# V_6.net
KiCad netlist of a schematic drawn in Altium Designer
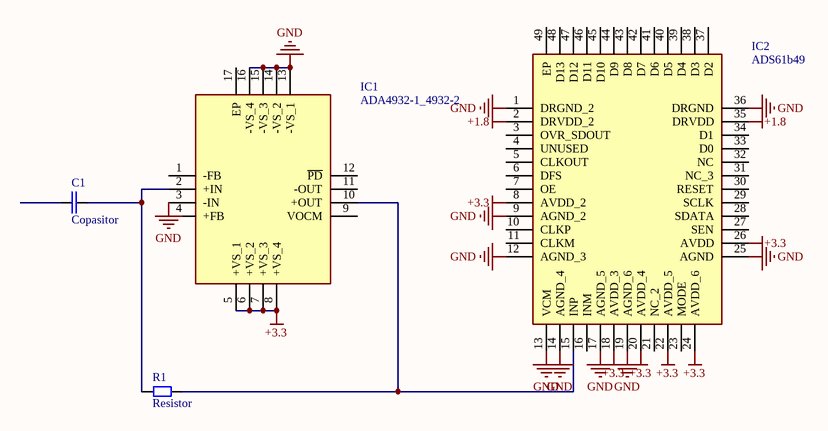
[diagram p0: V_6.SchDoc]

(export (version "E")
  (design (tool "Eeschema 10.0.6"))
  (components
    (comp (ref "C1") (value "Copasitor") (footprint "Copasitor") (libsource (lib "V__6") (part "Copasitor")))
    (comp (ref "IC1")
      (value "ADA4932-1_4932-2")
      (footprint "ADA4932-1")
      (libsource (lib "V__6") (part "ADA4932-1_4932-2"))
    )
    (comp (ref "IC2") (value "ADS61b49") (footprint "ADS61b49") (libsource (lib "V__6") (part "ADS61b49")))
    (comp (ref "R1") (value "Resistor") (footprint "Resistor") (libsource (lib "V__6") (part "Resistor")))
  )
  (nets
    (net (code "1") (name "+1.8") (class "Default")
      (node (ref "IC2") (pin "2") (pinfunction "DRVDD_2_2") (pintype "passive"))
      (node (ref "IC2") (pin "35") (pinfunction "DRVDD_35") (pintype "passive"))
    )
    (net (code "2") (name "+3.3") (class "Default")
      (node (ref "IC1") (pin "5") (pinfunction "+VS_1_5") (pintype "passive"))
      (node (ref "IC1") (pin "6") (pinfunction "+VS_2_6") (pintype "passive"))
      (node (ref "IC1") (pin "7") (pinfunction "+VS_3_7") (pintype "passive"))
      (node (ref "IC1") (pin "8") (pinfunction "+VS_4_8") (pintype "passive"))
      (node (ref "IC2") (pin "18") (pinfunction "AVDD_3_18") (pintype "passive"))
      (node (ref "IC2") (pin "20") (pinfunction "AVDD_4_20") (pintype "passive"))
      (node (ref "IC2") (pin "22") (pinfunction "AVDD_5_22") (pintype "passive"))
      (node (ref "IC2") (pin "24") (pinfunction "AVDD_6_24") (pintype "passive"))
      (node (ref "IC2") (pin "26") (pinfunction "AVDD_26") (pintype "passive"))
      (node (ref "IC2") (pin "8") (pinfunction "AVDD_2_8") (pintype "passive"))
    )
    (net (code "3") (name "GND") (class "Default")
      (node (ref "IC1") (pin "13") (pinfunction "-VS_1_13") (pintype "passive"))
      (node (ref "IC1") (pin "14") (pinfunction "-VS_2_14") (pintype "passive"))
      (node (ref "IC1") (pin "15") (pinfunction "-VS_3_15") (pintype "passive"))
      (node (ref "IC1") (pin "16") (pinfunction "-VS_4_16") (pintype "passive"))
      (node (ref "IC1") (pin "3") (pinfunction "-IN_3") (pintype "passive"))
      (node (ref "IC2") (pin "1") (pinfunction "DRGND_2_1") (pintype "passive"))
      (node (ref "IC2") (pin "12") (pinfunction "AGND_3_12") (pintype "passive"))
      (node (ref "IC2") (pin "13") (pinfunction "VCM_13") (pintype "passive"))
      (node (ref "IC2") (pin "14") (pinfunction "AGND_4_14") (pintype "passive"))
      (node (ref "IC2") (pin "17") (pinfunction "AGND_5_17") (pintype "passive"))
      (node (ref "IC2") (pin "19") (pinfunction "AGND_6_19") (pintype "passive"))
      (node (ref "IC2") (pin "25") (pinfunction "AGND_25") (pintype "passive"))
      (node (ref "IC2") (pin "36") (pinfunction "DRGND_36") (pintype "passive"))
      (node (ref "IC2") (pin "9") (pinfunction "AGND_2_9") (pintype "passive"))
    )
    (net (code "4") (name "Net-(IC1-+IN)") (class "Default")
      (node (ref "C1") (pin "2") (pintype "passive"))
      (node (ref "IC1") (pin "2") (pinfunction "+IN_2") (pintype "passive"))
      (node (ref "R1") (pin "1") (pintype "passive"))
    )
    (net (code "5") (name "Net-(IC1-+OUT)") (class "Default")
      (node (ref "IC1") (pin "10") (pinfunction "+OUT_10") (pintype "passive"))
      (node (ref "IC2") (pin "15") (pinfunction "INP_15") (pintype "passive"))
      (node (ref "R1") (pin "2") (pintype "passive"))
    )
    (net (code "6") (name "unconnected-(C1-Pad1)") (class "Default")
      (node (ref "C1") (pin "1") (pintype "passive"))
    )
    (net (code "7") (name "unconnected-(IC1-+FB-Pad4)") (class "Default")
      (node (ref "IC1") (pin "4") (pinfunction "+FB_4") (pintype "passive"))
    )
    (net (code "8") (name "unconnected-(IC1--FB-Pad1)") (class "Default")
      (node (ref "IC1") (pin "1") (pinfunction "-FB_1") (pintype "passive"))
    )
    (net (code "9") (name "unconnected-(IC1--OUT-Pad11)") (class "Default")
      (node (ref "IC1") (pin "11") (pinfunction "-OUT_11") (pintype "passive"))
    )
    (net (code "10") (name "unconnected-(IC1-EP-Pad17)") (class "Default")
      (node (ref "IC1") (pin "17") (pinfunction "EP_17") (pintype "passive"))
    )
    (net (code "11") (name "unconnected-(IC1-VOCM-Pad9)") (class "Default")
      (node (ref "IC1") (pin "9") (pinfunction "VOCM_9") (pintype "passive"))
    )
    (net (code "12") (name "unconnected-(IC1-~{PD}-Pad12)") (class "Default")
      (node (ref "IC1") (pin "12") (pinfunction "~{PD}_12") (pintype "passive"))
    )
    (net (code "13") (name "unconnected-(IC2-CLKM-Pad11)") (class "Default")
      (node (ref "IC2") (pin "11") (pinfunction "CLKM_11") (pintype "passive"))
    )
    (net (code "14") (name "unconnected-(IC2-CLKOUT-Pad5)") (class "Default")
      (node (ref "IC2") (pin "5") (pinfunction "CLKOUT_5") (pintype "passive"))
    )
    (net (code "15") (name "unconnected-(IC2-CLKP-Pad10)") (class "Default")
      (node (ref "IC2") (pin "10") (pinfunction "CLKP_10") (pintype "passive"))
    )
    (net (code "16") (name "unconnected-(IC2-D0-Pad33)") (class "Default")
      (node (ref "IC2") (pin "33") (pinfunction "D0_33") (pintype "passive"))
    )
    (net (code "17") (name "unconnected-(IC2-D1-Pad34)") (class "Default")
      (node (ref "IC2") (pin "34") (pinfunction "D1_34") (pintype "passive"))
    )
    (net (code "18") (name "unconnected-(IC2-D2-Pad37)") (class "Default")
      (node (ref "IC2") (pin "37") (pinfunction "D2_37") (pintype "passive"))
    )
    (net (code "19") (name "unconnected-(IC2-D3-Pad38)") (class "Default")
      (node (ref "IC2") (pin "38") (pinfunction "D3_38") (pintype "passive"))
    )
    (net (code "20") (name "unconnected-(IC2-D4-Pad39)") (class "Default")
      (node (ref "IC2") (pin "39") (pinfunction "D4_39") (pintype "passive"))
    )
    (net (code "21") (name "unconnected-(IC2-D5-Pad40)") (class "Default")
      (node (ref "IC2") (pin "40") (pinfunction "D5_40") (pintype "passive"))
    )
    (net (code "22") (name "unconnected-(IC2-D6-Pad41)") (class "Default")
      (node (ref "IC2") (pin "41") (pinfunction "D6_41") (pintype "passive"))
    )
    (net (code "23") (name "unconnected-(IC2-D7-Pad42)") (class "Default")
      (node (ref "IC2") (pin "42") (pinfunction "D7_42") (pintype "passive"))
    )
    (net (code "24") (name "unconnected-(IC2-D8-Pad43)") (class "Default")
      (node (ref "IC2") (pin "43") (pinfunction "D8_43") (pintype "passive"))
    )
    (net (code "25") (name "unconnected-(IC2-D9-Pad44)") (class "Default")
      (node (ref "IC2") (pin "44") (pinfunction "D9_44") (pintype "passive"))
    )
    (net (code "26") (name "unconnected-(IC2-D10-Pad45)") (class "Default")
      (node (ref "IC2") (pin "45") (pinfunction "D10_45") (pintype "passive"))
    )
    (net (code "27") (name "unconnected-(IC2-D11-Pad46)") (class "Default")
      (node (ref "IC2") (pin "46") (pinfunction "D11_46") (pintype "passive"))
    )
    (net (code "28") (name "unconnected-(IC2-D12-Pad47)") (class "Default")
      (node (ref "IC2") (pin "47") (pinfunction "D12_47") (pintype "passive"))
    )
    (net (code "29") (name "unconnected-(IC2-D13-Pad48)") (class "Default")
      (node (ref "IC2") (pin "48") (pinfunction "D13_48") (pintype "passive"))
    )
    (net (code "30") (name "unconnected-(IC2-DFS-Pad6)") (class "Default")
      (node (ref "IC2") (pin "6") (pinfunction "DFS_6") (pintype "passive"))
    )
    (net (code "31") (name "unconnected-(IC2-EP-Pad49)") (class "Default")
      (node (ref "IC2") (pin "49") (pinfunction "EP_49") (pintype "passive"))
    )
    (net (code "32") (name "unconnected-(IC2-INM-Pad16)") (class "Default")
      (node (ref "IC2") (pin "16") (pinfunction "INM_16") (pintype "passive"))
    )
    (net (code "33") (name "unconnected-(IC2-MODE-Pad23)") (class "Default")
      (node (ref "IC2") (pin "23") (pinfunction "MODE_23") (pintype "passive"))
    )
    (net (code "34") (name "unconnected-(IC2-NC-Pad32)") (class "Default")
      (node (ref "IC2") (pin "32") (pinfunction "NC_32") (pintype "passive"))
    )
    (net (code "35") (name "unconnected-(IC2-NC_2-Pad21)") (class "Default")
      (node (ref "IC2") (pin "21") (pinfunction "NC_2_21") (pintype "passive"))
    )
    (net (code "36") (name "unconnected-(IC2-NC_3-Pad31)") (class "Default")
      (node (ref "IC2") (pin "31") (pinfunction "NC_3_31") (pintype "passive"))
    )
    (net (code "37") (name "unconnected-(IC2-OE-Pad7)") (class "Default")
      (node (ref "IC2") (pin "7") (pinfunction "OE_7") (pintype "passive"))
    )
    (net (code "38") (name "unconnected-(IC2-OVR_SDOUT-Pad3)") (class "Default")
      (node (ref "IC2") (pin "3") (pinfunction "OVR_SDOUT_3") (pintype "passive"))
    )
    (net (code "39") (name "unconnected-(IC2-RESET-Pad30)") (class "Default")
      (node (ref "IC2") (pin "30") (pinfunction "RESET_30") (pintype "passive"))
    )
    (net (code "40") (name "unconnected-(IC2-SCLK-Pad29)") (class "Default")
      (node (ref "IC2") (pin "29") (pinfunction "SCLK_29") (pintype "passive"))
    )
    (net (code "41") (name "unconnected-(IC2-SDATA-Pad28)") (class "Default")
      (node (ref "IC2") (pin "28") (pinfunction "SDATA_28") (pintype "passive"))
    )
    (net (code "42") (name "unconnected-(IC2-SEN-Pad27)") (class "Default")
      (node (ref "IC2") (pin "27") (pinfunction "SEN_27") (pintype "passive"))
    )
    (net (code "43") (name "unconnected-(IC2-UNUSED-Pad4)") (class "Default")
      (node (ref "IC2") (pin "4") (pinfunction "UNUSED_4") (pintype "passive"))
    )
  )
)
